# IR60-19_5GF.net
KiCad netlist of a schematic drawn in Altium Designer
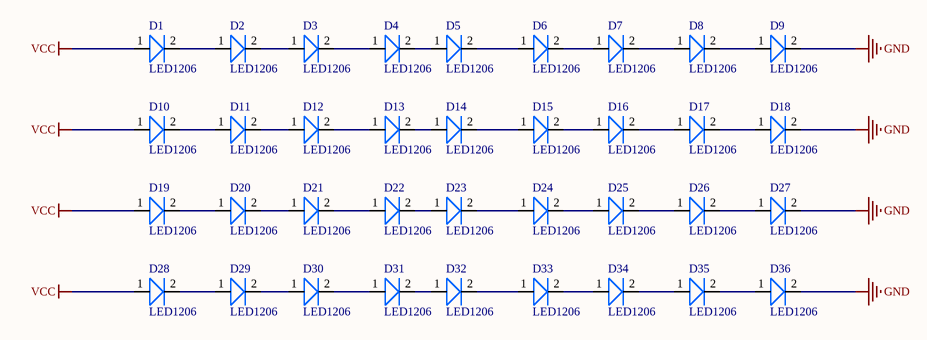
[diagram p0: IR60-19_5GF.SchDoc]

(export (version "E")
  (design (tool "Eeschema 10.0.6"))
  (components
    (comp (ref "D1")
      (value "LED1206")
      (footprint "myPCBLib:IRLED2835M")
      (libsource (lib "mySchLib") (part "LED1206"))
    )
    (comp (ref "D2")
      (value "LED1206")
      (footprint "myPCBLib:IRLED2835M")
      (libsource (lib "mySchLib") (part "LED1206"))
    )
    (comp (ref "D3")
      (value "LED1206")
      (footprint "myPCBLib:IRLED2835M")
      (libsource (lib "mySchLib") (part "LED1206"))
    )
    (comp (ref "D4")
      (value "LED1206")
      (footprint "myPCBLib:IRLED2835M")
      (libsource (lib "mySchLib") (part "LED1206"))
    )
    (comp (ref "D5")
      (value "LED1206")
      (footprint "myPCBLib:IRLED2835M")
      (libsource (lib "mySchLib") (part "LED1206"))
    )
    (comp (ref "D6")
      (value "LED1206")
      (footprint "myPCBLib:IRLED2835M")
      (libsource (lib "mySchLib") (part "LED1206"))
    )
    (comp (ref "D7")
      (value "LED1206")
      (footprint "myPCBLib:IRLED2835M")
      (libsource (lib "mySchLib") (part "LED1206"))
    )
    (comp (ref "D8")
      (value "LED1206")
      (footprint "myPCBLib:IRLED2835M")
      (libsource (lib "mySchLib") (part "LED1206"))
    )
    (comp (ref "D9")
      (value "LED1206")
      (footprint "myPCBLib:IRLED2835M")
      (libsource (lib "mySchLib") (part "LED1206"))
    )
    (comp (ref "D10")
      (value "LED1206")
      (footprint "myPCBLib:IRLED2835M")
      (libsource (lib "mySchLib") (part "LED1206"))
    )
    (comp (ref "D11")
      (value "LED1206")
      (footprint "myPCBLib:IRLED2835M")
      (libsource (lib "mySchLib") (part "LED1206"))
    )
    (comp (ref "D12")
      (value "LED1206")
      (footprint "myPCBLib:IRLED2835M")
      (libsource (lib "mySchLib") (part "LED1206"))
    )
    (comp (ref "D13")
      (value "LED1206")
      (footprint "myPCBLib:IRLED2835M")
      (libsource (lib "mySchLib") (part "LED1206"))
    )
    (comp (ref "D14")
      (value "LED1206")
      (footprint "myPCBLib:IRLED2835M")
      (libsource (lib "mySchLib") (part "LED1206"))
    )
    (comp (ref "D15")
      (value "LED1206")
      (footprint "myPCBLib:IRLED2835M")
      (libsource (lib "mySchLib") (part "LED1206"))
    )
    (comp (ref "D16")
      (value "LED1206")
      (footprint "myPCBLib:IRLED2835M")
      (libsource (lib "mySchLib") (part "LED1206"))
    )
    (comp (ref "D17")
      (value "LED1206")
      (footprint "myPCBLib:IRLED2835M")
      (libsource (lib "mySchLib") (part "LED1206"))
    )
    (comp (ref "D18")
      (value "LED1206")
      (footprint "myPCBLib:IRLED2835M")
      (libsource (lib "mySchLib") (part "LED1206"))
    )
    (comp (ref "D19")
      (value "LED1206")
      (footprint "myPCBLib:IRLED2835M")
      (libsource (lib "mySchLib") (part "LED1206"))
    )
    (comp (ref "D20")
      (value "LED1206")
      (footprint "myPCBLib:IRLED2835M")
      (libsource (lib "mySchLib") (part "LED1206"))
    )
    (comp (ref "D21")
      (value "LED1206")
      (footprint "myPCBLib:IRLED2835M")
      (libsource (lib "mySchLib") (part "LED1206"))
    )
    (comp (ref "D22")
      (value "LED1206")
      (footprint "myPCBLib:IRLED2835M")
      (libsource (lib "mySchLib") (part "LED1206"))
    )
    (comp (ref "D23")
      (value "LED1206")
      (footprint "myPCBLib:IRLED2835M")
      (libsource (lib "mySchLib") (part "LED1206"))
    )
    (comp (ref "D24")
      (value "LED1206")
      (footprint "myPCBLib:IRLED2835M")
      (libsource (lib "mySchLib") (part "LED1206"))
    )
    (comp (ref "D25")
      (value "LED1206")
      (footprint "myPCBLib:IRLED2835M")
      (libsource (lib "mySchLib") (part "LED1206"))
    )
    (comp (ref "D26")
      (value "LED1206")
      (footprint "myPCBLib:IRLED2835M")
      (libsource (lib "mySchLib") (part "LED1206"))
    )
    (comp (ref "D27")
      (value "LED1206")
      (footprint "myPCBLib:IRLED2835M")
      (libsource (lib "mySchLib") (part "LED1206"))
    )
    (comp (ref "D28")
      (value "LED1206")
      (footprint "myPCBLib:IRLED2835M")
      (libsource (lib "mySchLib") (part "LED1206"))
    )
    (comp (ref "D29")
      (value "LED1206")
      (footprint "myPCBLib:IRLED2835M")
      (libsource (lib "mySchLib") (part "LED1206"))
    )
    (comp (ref "D30")
      (value "LED1206")
      (footprint "myPCBLib:IRLED2835M")
      (libsource (lib "mySchLib") (part "LED1206"))
    )
    (comp (ref "D31")
      (value "LED1206")
      (footprint "myPCBLib:IRLED2835M")
      (libsource (lib "mySchLib") (part "LED1206"))
    )
    (comp (ref "D32")
      (value "LED1206")
      (footprint "myPCBLib:IRLED2835M")
      (libsource (lib "mySchLib") (part "LED1206"))
    )
    (comp (ref "D33")
      (value "LED1206")
      (footprint "myPCBLib:IRLED2835M")
      (libsource (lib "mySchLib") (part "LED1206"))
    )
    (comp (ref "D34")
      (value "LED1206")
      (footprint "myPCBLib:IRLED2835M")
      (libsource (lib "mySchLib") (part "LED1206"))
    )
    (comp (ref "D35")
      (value "LED1206")
      (footprint "myPCBLib:IRLED2835M")
      (libsource (lib "mySchLib") (part "LED1206"))
    )
    (comp (ref "D36")
      (value "LED1206")
      (footprint "myPCBLib:IRLED2835M")
      (libsource (lib "mySchLib") (part "LED1206"))
    )
  )
  (nets
    (net (code "1") (name "GND") (class "Default")
      (node (ref "D18") (pin "2") (pinfunction "-_2") (pintype "open_collector"))
      (node (ref "D27") (pin "2") (pinfunction "-_2") (pintype "open_collector"))
      (node (ref "D36") (pin "2") (pinfunction "-_2") (pintype "open_collector"))
      (node (ref "D9") (pin "2") (pinfunction "-_2") (pintype "open_collector"))
    )
    (net (code "2") (name "Net-(D1--)") (class "Default")
      (node (ref "D1") (pin "2") (pinfunction "-_2") (pintype "open_collector"))
      (node (ref "D2") (pin "1") (pinfunction "+_1") (pintype "passive"))
    )
    (net (code "3") (name "Net-(D2--)") (class "Default")
      (node (ref "D2") (pin "2") (pinfunction "-_2") (pintype "open_collector"))
      (node (ref "D3") (pin "1") (pinfunction "+_1") (pintype "passive"))
    )
    (net (code "4") (name "Net-(D3--)") (class "Default")
      (node (ref "D3") (pin "2") (pinfunction "-_2") (pintype "open_collector"))
      (node (ref "D4") (pin "1") (pinfunction "+_1") (pintype "passive"))
    )
    (net (code "5") (name "Net-(D4--)") (class "Default")
      (node (ref "D4") (pin "2") (pinfunction "-_2") (pintype "open_collector"))
      (node (ref "D5") (pin "1") (pinfunction "+_1") (pintype "passive"))
    )
    (net (code "6") (name "Net-(D5--)") (class "Default")
      (node (ref "D5") (pin "2") (pinfunction "-_2") (pintype "open_collector"))
      (node (ref "D6") (pin "1") (pinfunction "+_1") (pintype "passive"))
    )
    (net (code "7") (name "Net-(D6--)") (class "Default")
      (node (ref "D6") (pin "2") (pinfunction "-_2") (pintype "open_collector"))
      (node (ref "D7") (pin "1") (pinfunction "+_1") (pintype "passive"))
    )
    (net (code "8") (name "Net-(D7--)") (class "Default")
      (node (ref "D7") (pin "2") (pinfunction "-_2") (pintype "open_collector"))
      (node (ref "D8") (pin "1") (pinfunction "+_1") (pintype "passive"))
    )
    (net (code "9") (name "Net-(D8--)") (class "Default")
      (node (ref "D8") (pin "2") (pinfunction "-_2") (pintype "open_collector"))
      (node (ref "D9") (pin "1") (pinfunction "+_1") (pintype "passive"))
    )
    (net (code "10") (name "Net-(D10--)") (class "Default")
      (node (ref "D10") (pin "2") (pinfunction "-_2") (pintype "open_collector"))
      (node (ref "D11") (pin "1") (pinfunction "+_1") (pintype "passive"))
    )
    (net (code "11") (name "Net-(D11--)") (class "Default")
      (node (ref "D11") (pin "2") (pinfunction "-_2") (pintype "open_collector"))
      (node (ref "D12") (pin "1") (pinfunction "+_1") (pintype "passive"))
    )
    (net (code "12") (name "Net-(D12--)") (class "Default")
      (node (ref "D12") (pin "2") (pinfunction "-_2") (pintype "open_collector"))
      (node (ref "D13") (pin "1") (pinfunction "+_1") (pintype "passive"))
    )
    (net (code "13") (name "Net-(D13--)") (class "Default")
      (node (ref "D13") (pin "2") (pinfunction "-_2") (pintype "open_collector"))
      (node (ref "D14") (pin "1") (pinfunction "+_1") (pintype "passive"))
    )
    (net (code "14") (name "Net-(D14--)") (class "Default")
      (node (ref "D14") (pin "2") (pinfunction "-_2") (pintype "open_collector"))
      (node (ref "D15") (pin "1") (pinfunction "+_1") (pintype "passive"))
    )
    (net (code "15") (name "Net-(D15--)") (class "Default")
      (node (ref "D15") (pin "2") (pinfunction "-_2") (pintype "open_collector"))
      (node (ref "D16") (pin "1") (pinfunction "+_1") (pintype "passive"))
    )
    (net (code "16") (name "Net-(D16--)") (class "Default")
      (node (ref "D16") (pin "2") (pinfunction "-_2") (pintype "open_collector"))
      (node (ref "D17") (pin "1") (pinfunction "+_1") (pintype "passive"))
    )
    (net (code "17") (name "Net-(D17--)") (class "Default")
      (node (ref "D17") (pin "2") (pinfunction "-_2") (pintype "open_collector"))
      (node (ref "D18") (pin "1") (pinfunction "+_1") (pintype "passive"))
    )
    (net (code "18") (name "Net-(D19--)") (class "Default")
      (node (ref "D19") (pin "2") (pinfunction "-_2") (pintype "open_collector"))
      (node (ref "D20") (pin "1") (pinfunction "+_1") (pintype "passive"))
    )
    (net (code "19") (name "Net-(D20--)") (class "Default")
      (node (ref "D20") (pin "2") (pinfunction "-_2") (pintype "open_collector"))
      (node (ref "D21") (pin "1") (pinfunction "+_1") (pintype "passive"))
    )
    (net (code "20") (name "Net-(D21--)") (class "Default")
      (node (ref "D21") (pin "2") (pinfunction "-_2") (pintype "open_collector"))
      (node (ref "D22") (pin "1") (pinfunction "+_1") (pintype "passive"))
    )
    (net (code "21") (name "Net-(D22--)") (class "Default")
      (node (ref "D22") (pin "2") (pinfunction "-_2") (pintype "open_collector"))
      (node (ref "D23") (pin "1") (pinfunction "+_1") (pintype "passive"))
    )
    (net (code "22") (name "Net-(D23--)") (class "Default")
      (node (ref "D23") (pin "2") (pinfunction "-_2") (pintype "open_collector"))
      (node (ref "D24") (pin "1") (pinfunction "+_1") (pintype "passive"))
    )
    (net (code "23") (name "Net-(D24--)") (class "Default")
      (node (ref "D24") (pin "2") (pinfunction "-_2") (pintype "open_collector"))
      (node (ref "D25") (pin "1") (pinfunction "+_1") (pintype "passive"))
    )
    (net (code "24") (name "Net-(D25--)") (class "Default")
      (node (ref "D25") (pin "2") (pinfunction "-_2") (pintype "open_collector"))
      (node (ref "D26") (pin "1") (pinfunction "+_1") (pintype "passive"))
    )
    (net (code "25") (name "Net-(D26--)") (class "Default")
      (node (ref "D26") (pin "2") (pinfunction "-_2") (pintype "open_collector"))
      (node (ref "D27") (pin "1") (pinfunction "+_1") (pintype "passive"))
    )
    (net (code "26") (name "Net-(D28--)") (class "Default")
      (node (ref "D28") (pin "2") (pinfunction "-_2") (pintype "open_collector"))
      (node (ref "D29") (pin "1") (pinfunction "+_1") (pintype "passive"))
    )
    (net (code "27") (name "Net-(D29--)") (class "Default")
      (node (ref "D29") (pin "2") (pinfunction "-_2") (pintype "open_collector"))
      (node (ref "D30") (pin "1") (pinfunction "+_1") (pintype "passive"))
    )
    (net (code "28") (name "Net-(D30--)") (class "Default")
      (node (ref "D30") (pin "2") (pinfunction "-_2") (pintype "open_collector"))
      (node (ref "D31") (pin "1") (pinfunction "+_1") (pintype "passive"))
    )
    (net (code "29") (name "Net-(D31--)") (class "Default")
      (node (ref "D31") (pin "2") (pinfunction "-_2") (pintype "open_collector"))
      (node (ref "D32") (pin "1") (pinfunction "+_1") (pintype "passive"))
    )
    (net (code "30") (name "Net-(D32--)") (class "Default")
      (node (ref "D32") (pin "2") (pinfunction "-_2") (pintype "open_collector"))
      (node (ref "D33") (pin "1") (pinfunction "+_1") (pintype "passive"))
    )
    (net (code "31") (name "Net-(D33--)") (class "Default")
      (node (ref "D33") (pin "2") (pinfunction "-_2") (pintype "open_collector"))
      (node (ref "D34") (pin "1") (pinfunction "+_1") (pintype "passive"))
    )
    (net (code "32") (name "Net-(D34--)") (class "Default")
      (node (ref "D34") (pin "2") (pinfunction "-_2") (pintype "open_collector"))
      (node (ref "D35") (pin "1") (pinfunction "+_1") (pintype "passive"))
    )
    (net (code "33") (name "Net-(D35--)") (class "Default")
      (node (ref "D35") (pin "2") (pinfunction "-_2") (pintype "open_collector"))
      (node (ref "D36") (pin "1") (pinfunction "+_1") (pintype "passive"))
    )
    (net (code "34") (name "VCC") (class "Default")
      (node (ref "D1") (pin "1") (pinfunction "+_1") (pintype "passive"))
      (node (ref "D10") (pin "1") (pinfunction "+_1") (pintype "passive"))
      (node (ref "D19") (pin "1") (pinfunction "+_1") (pintype "passive"))
      (node (ref "D28") (pin "1") (pinfunction "+_1") (pintype "passive"))
    )
  )
)
